# I2C_Shield.net
KiCad netlist of a schematic drawn in Altium Designer
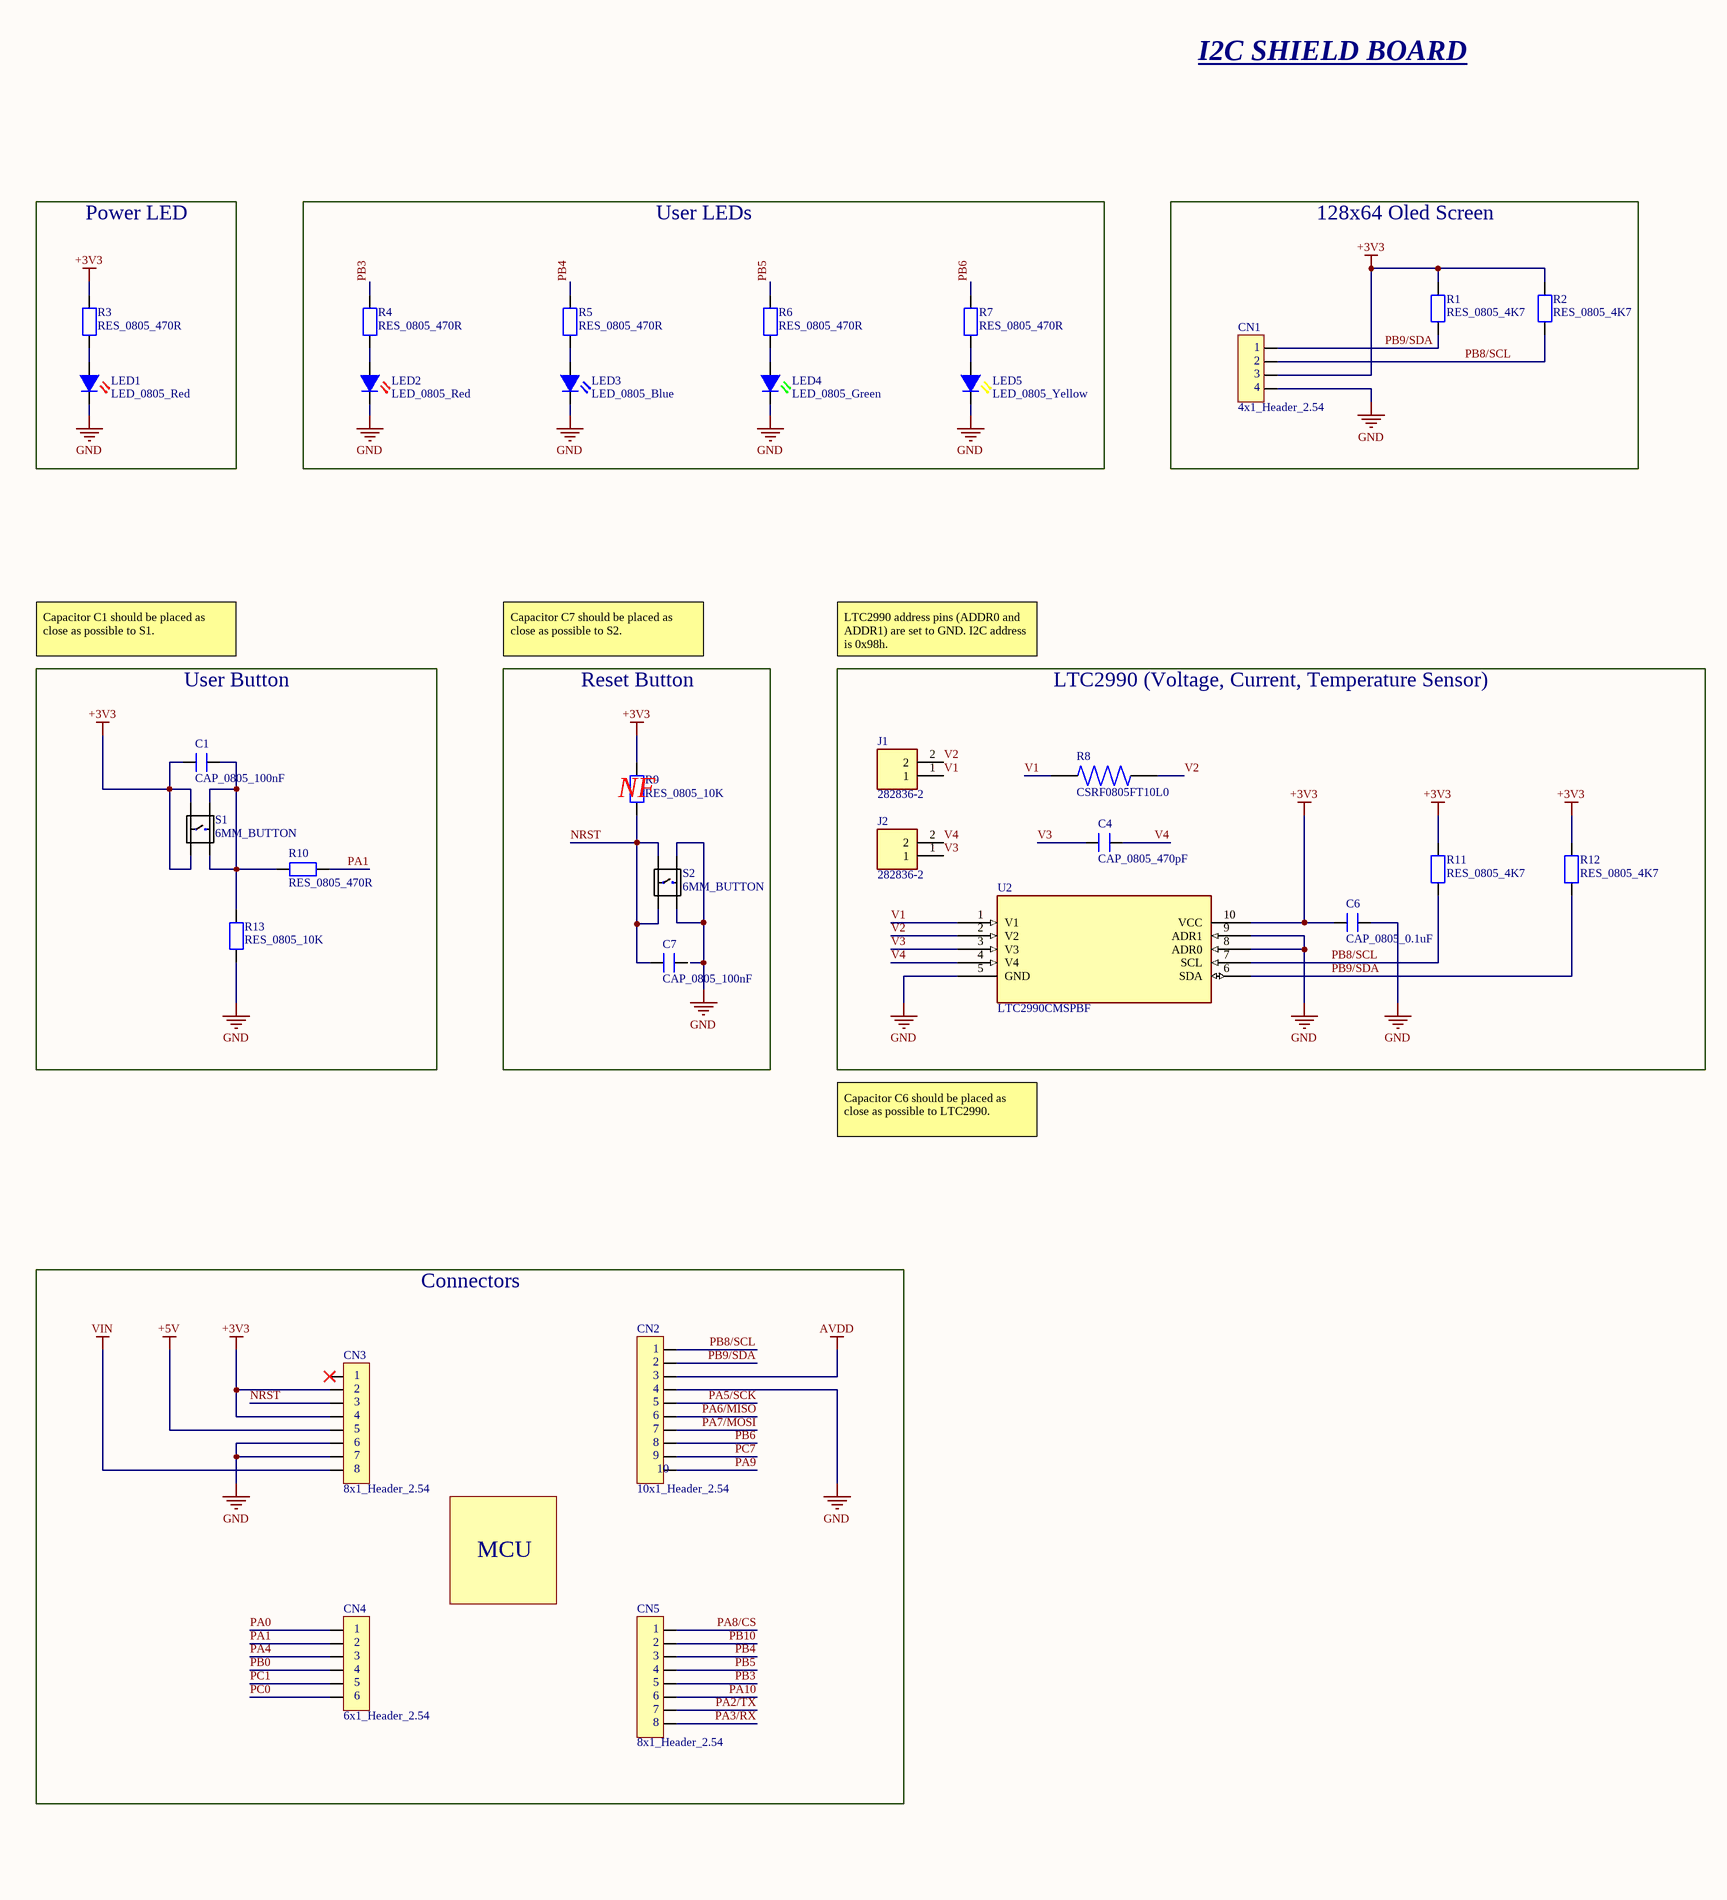
[diagram p0: I2C_Shield.SchDoc, left]
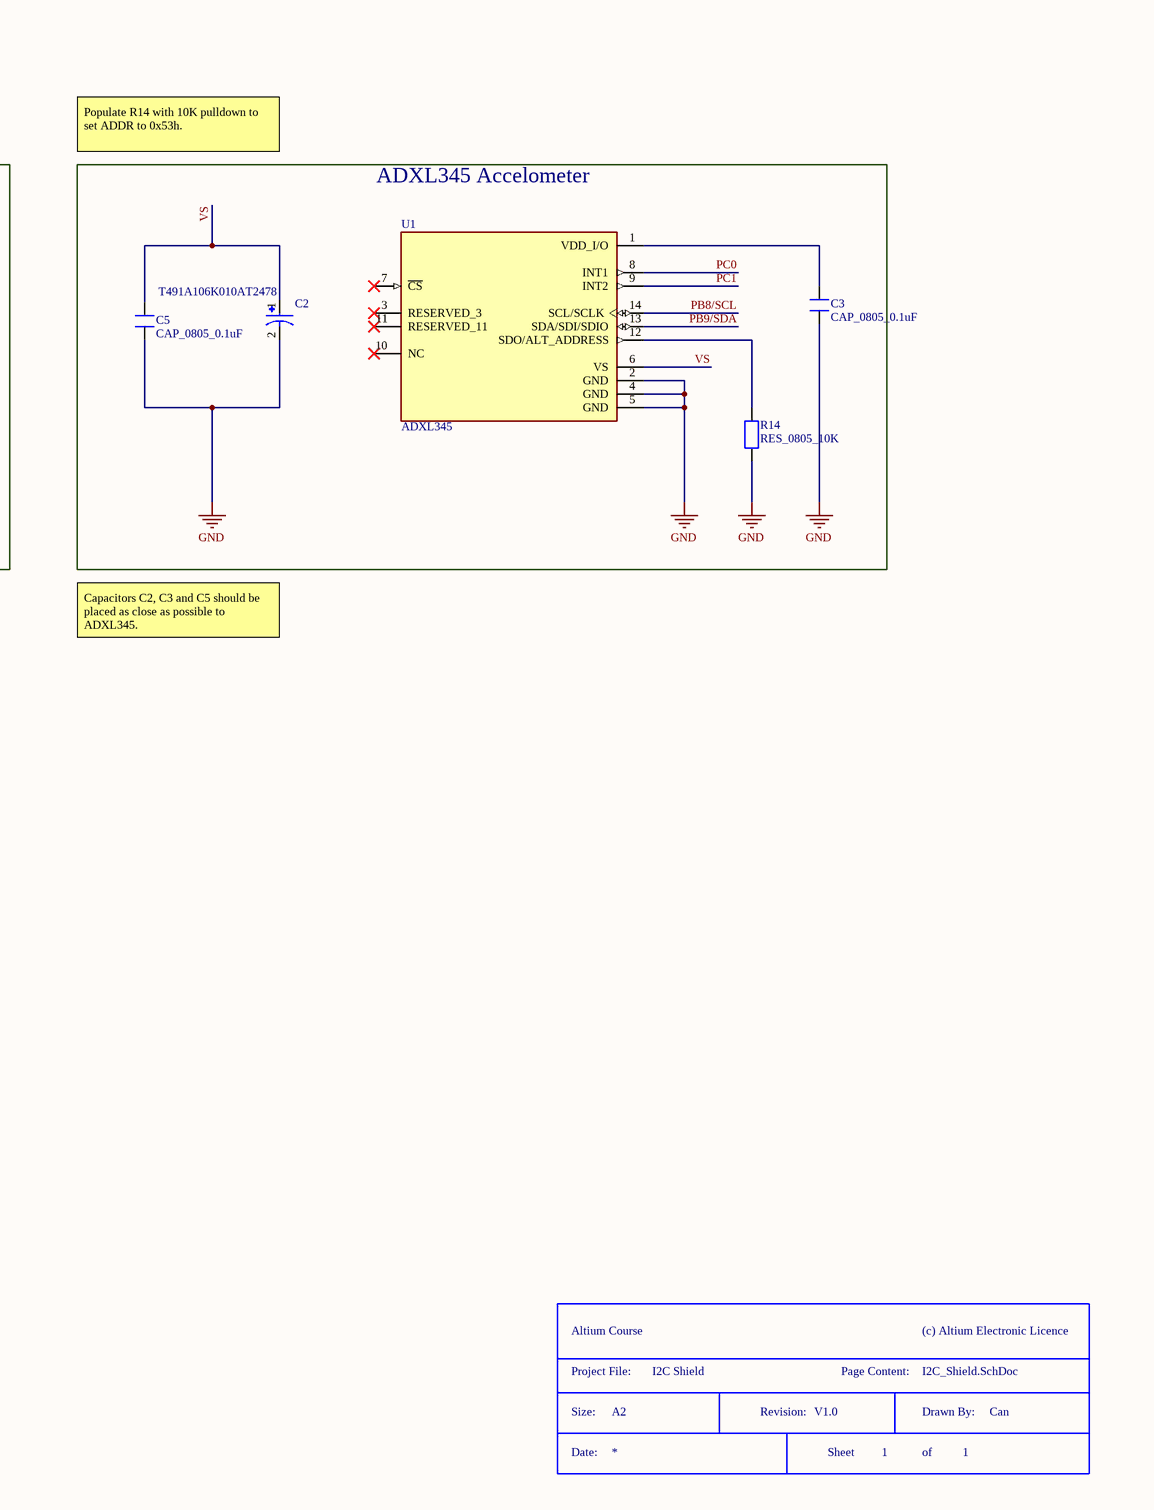
[diagram p1: I2C_Shield.SchDoc, right]

(export (version "E")
  (design (tool "Eeschema 10.0.6"))
  (components
    (comp (ref "*") (value "Title Block") (libsource (lib "I2C_Shield") (part "Title Block")))
    (comp (ref "C1")
      (value "CAP_0805_100nF")
      (footprint "CAP_0805")
      (description "0805 100nF 16VDC ±10% X7R")
      (fields (field (name "MANUFACTURER") "CC0805KRX7R7BB104") (field (name "TOLERANCE") "10%"))
      (libsource (lib "I2C_Shield") (part "CAP_0805_100nF"))
    )
    (comp (ref "C2")
      (value "T491A106K010AT2478")
      (footprint "CAPMP3216X180N")
      (description "10 ÂµF Molded Tantalum Capacitors 10 V 1206 (3216 Metric) 3.8Ohm")
      (fields (field (name "MF") "KEMET"))
      (libsource (lib "tantalum10uF") (part "T491A106K010AT2478"))
    )
    (comp (ref "C3")
      (value "CAP_0805_0.1uF")
      (footprint "CAP_0805")
      (description "0805 0.1uF 16VDC ±10% X7R")
      (fields (field (name "MANUFACTURER") "CC0805KRX7R7BB104") (field (name "TOLERANCE") "10%"))
      (libsource (lib "I2C_Shield") (part "CAP_0805_0.1uF"))
    )
    (comp (ref "C4")
      (value "CAP_0805_470pF")
      (footprint "CAP_0805")
      (description "0805 470pF 16VDC ±10% X7R")
      (fields (field (name "MANUFACTURER") "CC0805KRX7R7BB104") (field (name "TOLERANCE") "10%"))
      (libsource (lib "I2C_Shield") (part "CAP_0805_470pF"))
    )
    (comp (ref "C5")
      (value "CAP_0805_0.1uF")
      (footprint "CAP_0805")
      (description "0805 0.1uF 16VDC ±10% X7R")
      (fields (field (name "MANUFACTURER") "CC0805KRX7R7BB104") (field (name "TOLERANCE") "10%"))
      (libsource (lib "I2C_Shield") (part "CAP_0805_0.1uF"))
    )
    (comp (ref "C6")
      (value "CAP_0805_0.1uF")
      (footprint "CAP_0805")
      (description "0805 0.1uF 16VDC ±10% X7R")
      (fields (field (name "MANUFACTURER") "CC0805KRX7R7BB104") (field (name "TOLERANCE") "10%"))
      (libsource (lib "I2C_Shield") (part "CAP_0805_0.1uF"))
    )
    (comp (ref "C7")
      (value "CAP_0805_100nF")
      (footprint "CAP_0805")
      (description "0805 100nF 16VDC ±10% X7R")
      (fields (field (name "MANUFACTURER") "CC0805KRX7R7BB104") (field (name "TOLERANCE") "10%"))
      (libsource (lib "I2C_Shield") (part "CAP_0805_100nF"))
    )
    (comp (ref "CN1")
      (value "4x1_Header_2.54")
      (description "Oled Screen Header")
      (libsource (lib "I2C_Shield") (part "4x1_Header_2.54"))
    )
    (comp (ref "CN2")
      (value "10x1_Header_2.54")
      (footprint "10x1_2.54MM_HEADER")
      (libsource (lib "I2C_Shield") (part "10x1_Header_2.54"))
    )
    (comp (ref "CN3")
      (value "8x1_Header_2.54")
      (footprint "8x1_2.54MM_HEADER")
      (libsource (lib "I2C_Shield") (part "8x1_Header_2.54"))
    )
    (comp (ref "CN4")
      (value "6x1_Header_2.54")
      (footprint "6x1_2.54MM_HEADER")
      (libsource (lib "I2C_Shield") (part "6x1_Header_2.54"))
    )
    (comp (ref "CN5")
      (value "8x1_Header_2.54")
      (footprint "8x1_2.54MM_HEADER")
      (libsource (lib "") (part "8x1_Header_2.54_1"))
    )
    (comp (ref "J1")
      (value "282836-2")
      (footprint "TE_282836-2")
      (description "Connector, Terminal Block; Wire Receptacle; 2 Pos.; 16-30 AWG; 0.197 in. CL; Sid")
      (fields (field (name "MF") "TE Connectivity"))
      (libsource (lib "terminalblock-2") (part "282836-2"))
    )
    (comp (ref "J2")
      (value "282836-2")
      (footprint "TE_282836-2")
      (description "Connector, Terminal Block; Wire Receptacle; 2 Pos.; 16-30 AWG; 0.197 in. CL; Sid")
      (fields (field (name "MF") "TE Connectivity"))
      (libsource (lib "terminalblock-2") (part "282836-2"))
    )
    (comp (ref "LED1")
      (value "LED_0805_Red")
      (footprint "LED_0805")
      (description "LED SMD 0805 RED 550mcd")
      (fields (field (name "MANUFACTURER") "HL-PSC-2012S9AC"))
      (libsource (lib "I2C_Shield") (part "LED_0805_Red"))
    )
    (comp (ref "LED2")
      (value "LED_0805_Red")
      (footprint "LED_0805")
      (description "LED SMD 0805 RED 550mcd")
      (fields (field (name "MANUFACTURER") "HL-PSC-2012S9AC"))
      (libsource (lib "I2C_Shield") (part "LED_0805_Red"))
    )
    (comp (ref "LED3")
      (value "LED_0805_Blue")
      (footprint "LED_0805")
      (description "LED SMD 0805 BLUE 550mcd")
      (fields (field (name "MANUFACTURER") "HL-PSC-2012H203BC"))
      (libsource (lib "I2C_Shield") (part "LED_0805_Blue"))
    )
    (comp (ref "LED4")
      (value "LED_0805_Green")
      (footprint "LED_0805")
      (description "LED SMD 0805 GREEN 550mcd")
      (fields (field (name "MANUFACTURER") "HL-PSC-2012U51GC"))
      (libsource (lib "I2C_Shield") (part "LED_0805_Green"))
    )
    (comp (ref "LED5")
      (value "LED_0805_Yellow")
      (footprint "LED_0805")
      (description "LED SMD 0805 YELLOW 550mcd")
      (fields (field (name "MANUFACTURER") "HL-PSC-2012S29YC"))
      (libsource (lib "I2C_Shield") (part "LED_0805_Yellow"))
    )
    (comp (ref "R1")
      (value "RES_0805_4K7")
      (footprint "RES_0805")
      (description "0805 4K7 Ohms 5% 1/8W")
      (fields (field (name "TOLERANCE") "5%") (field (name "MANUFACTURER") "RC0805JR-0710KL"))
      (libsource (lib "I2C_Shield") (part "RES_0805_4K7"))
    )
    (comp (ref "R2")
      (value "RES_0805_4K7")
      (footprint "RES_0805")
      (description "0805 4K7 Ohms 5% 1/8W")
      (fields (field (name "TOLERANCE") "5%") (field (name "MANUFACTURER") "RC0805JR-0710KL"))
      (libsource (lib "I2C_Shield") (part "RES_0805_4K7"))
    )
    (comp (ref "R3")
      (value "RES_0805_470R")
      (footprint "RES_0805")
      (description "0805 470 Ohms 5% 1/8W")
      (fields (field (name "MANUFACTURER") "RC0805JR-07470RL") (field (name "TOLERANCE") "5%"))
      (libsource (lib "I2C_Shield") (part "RES_0805_470R"))
    )
    (comp (ref "R4")
      (value "RES_0805_470R")
      (footprint "RES_0805")
      (description "0805 470 Ohms 5% 1/8W")
      (fields (field (name "MANUFACTURER") "RC0805JR-07470RL") (field (name "TOLERANCE") "5%"))
      (libsource (lib "I2C_Shield") (part "RES_0805_470R"))
    )
    (comp (ref "R5")
      (value "RES_0805_470R")
      (footprint "RES_0805")
      (description "0805 470 Ohms 5% 1/8W")
      (fields (field (name "MANUFACTURER") "RC0805JR-07470RL") (field (name "TOLERANCE") "5%"))
      (libsource (lib "I2C_Shield") (part "RES_0805_470R"))
    )
    (comp (ref "R6")
      (value "RES_0805_470R")
      (footprint "RES_0805")
      (description "0805 470 Ohms 5% 1/8W")
      (fields (field (name "MANUFACTURER") "RC0805JR-07470RL") (field (name "TOLERANCE") "5%"))
      (libsource (lib "I2C_Shield") (part "RES_0805_470R"))
    )
    (comp (ref "R7")
      (value "RES_0805_470R")
      (footprint "RES_0805")
      (description "0805 470 Ohms 5% 1/8W")
      (fields (field (name "MANUFACTURER") "RC0805JR-07470RL") (field (name "TOLERANCE") "5%"))
      (libsource (lib "I2C_Shield") (part "RES_0805_470R"))
    )
    (comp (ref "R8")
      (value "CSRF0805FT10L0")
      (footprint "RESC2113X85N")
      (fields (field (name "MF") "Stackpole Electronics"))
      (libsource (lib "CSRF0805FT10L0") (part "CSRF0805FT10L0"))
    )
    (comp (ref "R9")
      (value "RES_0805_10K")
      (footprint "RES_0805")
      (description "0805 10K Ohms 5% 1/8W")
      (fields (field (name "TOLERANCE") "5%") (field (name "MANUFACTURER") "RC0805JR-0710KL"))
      (libsource (lib "I2C_Shield") (part "RES_0805_10K"))
    )
    (comp (ref "R10")
      (value "RES_0805_470R")
      (footprint "RES_0805")
      (description "0805 470 Ohms 5% 1/8W")
      (fields (field (name "MANUFACTURER") "RC0805JR-07470RL") (field (name "TOLERANCE") "5%"))
      (libsource (lib "I2C_Shield") (part "RES_0805_470R"))
    )
    (comp (ref "R11")
      (value "RES_0805_4K7")
      (footprint "RES_0805")
      (description "0805 4K7 Ohms 5% 1/8W")
      (fields (field (name "TOLERANCE") "5%") (field (name "MANUFACTURER") "RC0805JR-0710KL"))
      (libsource (lib "I2C_Shield") (part "RES_0805_4K7"))
    )
    (comp (ref "R12")
      (value "RES_0805_4K7")
      (footprint "RES_0805")
      (description "0805 4K7 Ohms 5% 1/8W")
      (fields (field (name "TOLERANCE") "5%") (field (name "MANUFACTURER") "RC0805JR-0710KL"))
      (libsource (lib "I2C_Shield") (part "RES_0805_4K7"))
    )
    (comp (ref "R13")
      (value "RES_0805_10K")
      (footprint "RES_0805")
      (description "0805 10K Ohms 5% 1/8W")
      (fields (field (name "TOLERANCE") "5%") (field (name "MANUFACTURER") "RC0805JR-0710KL"))
      (libsource (lib "I2C_Shield") (part "RES_0805_10K"))
    )
    (comp (ref "R14")
      (value "RES_0805_10K")
      (footprint "RES_0805")
      (description "0805 10K Ohms 5% 1/8W")
      (fields (field (name "TOLERANCE") "5%") (field (name "MANUFACTURER") "RC0805JR-0710KL"))
      (libsource (lib "I2C_Shield") (part "RES_0805_10K"))
    )
    (comp (ref "S1")
      (value "6MM_BUTTON")
      (footprint "6MM_TACTILE_SWITCH")
      (description "SWITCH TACT 6x6MM")
      (fields (field (name "MANUFACTURER") "DS1042-03-116-KKR-250-10"))
      (libsource (lib "I2C_Shield") (part "6MM_BUTTON"))
    )
    (comp (ref "S2")
      (value "6MM_BUTTON")
      (footprint "6MM_TACTILE_SWITCH")
      (description "SWITCH TACT 6x6MM")
      (fields (field (name "MANUFACTURER") "DS1042-03-116-KKR-250-10"))
      (libsource (lib "I2C_Shield") (part "6MM_BUTTON"))
    )
    (comp (ref "U1")
      (value "ADXL345")
      (footprint "PQFN80P500X300X100-14N")
      (description "Accelerometer X, Y, Z Axis ±2g, 4g, 8g, 16g 0.05Hz ~ 1.6kHz 14-LGA (3x5)")
      (fields (field (name "MF") "Analog Devices, Inc."))
      (libsource (lib "ADXL345") (part "ADXL345"))
    )
    (comp (ref "U2")
      (value "LTC2990CMSPBF")
      (footprint "MSOP-10_MS")
      (fields (field (name "MF") "Analog Devices") (field (name "MP") "LTC2990CMS#PBF"))
      (libsource (lib "LTC2990CMSPBF") (part "LTC2990CMSPBF"))
    )
  )
  (nets
    (net (code "1") (name "+3V3") (class "Default")
      (node (ref "C1") (pin "1") (pinfunction "1_1") (pintype "passive"))
      (node (ref "C6") (pin "1") (pinfunction "1_1") (pintype "passive"))
      (node (ref "CN1") (pin "2") (pinfunction "2_2") (pintype "passive"))
      (node (ref "CN3") (pin "2") (pinfunction "2_2") (pintype "passive"))
      (node (ref "CN3") (pin "4") (pinfunction "4_4") (pintype "passive"))
      (node (ref "R1") (pin "2") (pinfunction "2_2") (pintype "passive"))
      (node (ref "R11") (pin "1") (pinfunction "1_1") (pintype "passive"))
      (node (ref "R12") (pin "2") (pinfunction "2_2") (pintype "passive"))
      (node (ref "R2") (pin "2") (pinfunction "2_2") (pintype "passive"))
      (node (ref "R3") (pin "2") (pinfunction "2_2") (pintype "passive"))
      (node (ref "R9") (pin "2") (pinfunction "2_2") (pintype "passive"))
      (node (ref "S1") (pin "1") (pinfunction "1_1") (pintype "passive"))
      (node (ref "S1") (pin "3") (pinfunction "3_3") (pintype "passive"))
      (node (ref "U2") (pin "10") (pinfunction "VCC_10") (pintype "power_in"))
    )
    (net (code "2") (name "+5V") (class "Default")
      (node (ref "CN3") (pin "5") (pinfunction "5_5") (pintype "passive"))
    )
    (net (code "3") (name "/NRST") (class "Default")
      (node (ref "C7") (pin "1") (pinfunction "1_1") (pintype "passive"))
      (node (ref "CN3") (pin "3") (pinfunction "3_3") (pintype "passive"))
      (node (ref "R9") (pin "1") (pinfunction "1_1") (pintype "passive"))
      (node (ref "S2") (pin "1") (pinfunction "1_1") (pintype "passive"))
      (node (ref "S2") (pin "3") (pinfunction "3_3") (pintype "passive"))
    )
    (net (code "4") (name "/PA0") (class "Default")
      (node (ref "CN4") (pin "1") (pinfunction "1_1") (pintype "passive"))
    )
    (net (code "5") (name "/PA1") (class "Default")
      (node (ref "CN4") (pin "2") (pinfunction "2_2") (pintype "passive"))
      (node (ref "R10") (pin "2") (pinfunction "2_2") (pintype "passive"))
    )
    (net (code "6") (name "/PA2{slash}TX") (class "Default")
      (node (ref "CN5") (pin "7") (pinfunction "7_7") (pintype "passive"))
    )
    (net (code "7") (name "/PA3{slash}RX") (class "Default")
      (node (ref "CN5") (pin "8") (pinfunction "8_8") (pintype "passive"))
    )
    (net (code "8") (name "/PA4") (class "Default")
      (node (ref "CN4") (pin "3") (pinfunction "3_3") (pintype "passive"))
    )
    (net (code "9") (name "/PA5{slash}SCK") (class "Default")
      (node (ref "CN2") (pin "5") (pinfunction "5_5") (pintype "passive"))
    )
    (net (code "10") (name "/PA6{slash}MISO") (class "Default")
      (node (ref "CN2") (pin "6") (pinfunction "6_6") (pintype "passive"))
    )
    (net (code "11") (name "/PA7{slash}MOSI") (class "Default")
      (node (ref "CN2") (pin "7") (pinfunction "7_7") (pintype "passive"))
    )
    (net (code "12") (name "/PA8{slash}CS") (class "Default")
      (node (ref "CN5") (pin "1") (pinfunction "1_1") (pintype "passive"))
    )
    (net (code "13") (name "/PA9") (class "Default")
      (node (ref "CN2") (pin "10") (pinfunction "10_10") (pintype "passive"))
    )
    (net (code "14") (name "/PA10") (class "Default")
      (node (ref "CN5") (pin "6") (pinfunction "6_6") (pintype "passive"))
    )
    (net (code "15") (name "/PB0") (class "Default")
      (node (ref "CN4") (pin "4") (pinfunction "4_4") (pintype "passive"))
    )
    (net (code "16") (name "/PB3") (class "Default")
      (node (ref "CN5") (pin "5") (pinfunction "5_5") (pintype "passive"))
      (node (ref "R4") (pin "2") (pinfunction "2_2") (pintype "passive"))
    )
    (net (code "17") (name "/PB4") (class "Default")
      (node (ref "CN5") (pin "3") (pinfunction "3_3") (pintype "passive"))
      (node (ref "R5") (pin "2") (pinfunction "2_2") (pintype "passive"))
    )
    (net (code "18") (name "/PB5") (class "Default")
      (node (ref "CN5") (pin "4") (pinfunction "4_4") (pintype "passive"))
      (node (ref "R6") (pin "1") (pinfunction "1_1") (pintype "passive"))
    )
    (net (code "19") (name "/PB6") (class "Default")
      (node (ref "CN2") (pin "8") (pinfunction "8_8") (pintype "passive"))
      (node (ref "R7") (pin "2") (pinfunction "2_2") (pintype "passive"))
    )
    (net (code "20") (name "/PB8{slash}SCL") (class "Default")
      (node (ref "CN1") (pin "1") (pinfunction "1_1") (pintype "passive"))
      (node (ref "CN2") (pin "1") (pinfunction "1_1") (pintype "passive"))
      (node (ref "R11") (pin "2") (pinfunction "2_2") (pintype "passive"))
      (node (ref "R2") (pin "1") (pinfunction "1_1") (pintype "passive"))
      (node (ref "U1") (pin "14") (pinfunction "SCL/SCLK_14") (pintype "bidirectional"))
      (node (ref "U2") (pin "7") (pinfunction "SCL_7") (pintype "input"))
    )
    (net (code "21") (name "/PB9{slash}SDA") (class "Default")
      (node (ref "CN1") (pin "0") (pinfunction "0_0") (pintype "passive"))
      (node (ref "CN2") (pin "2") (pinfunction "2_2") (pintype "passive"))
      (node (ref "R1") (pin "1") (pinfunction "1_1") (pintype "passive"))
      (node (ref "R12") (pin "1") (pinfunction "1_1") (pintype "passive"))
      (node (ref "U1") (pin "13") (pinfunction "SDA/SDI/SDIO_13") (pintype "bidirectional"))
      (node (ref "U2") (pin "6") (pinfunction "SDA_6") (pintype "bidirectional"))
    )
    (net (code "22") (name "/PB10") (class "Default")
      (node (ref "CN5") (pin "2") (pinfunction "2_2") (pintype "passive"))
    )
    (net (code "23") (name "/PC0") (class "Default")
      (node (ref "CN4") (pin "6") (pinfunction "6_6") (pintype "passive"))
      (node (ref "U1") (pin "8") (pinfunction "INT1_8") (pintype "output"))
    )
    (net (code "24") (name "/PC1") (class "Default")
      (node (ref "CN4") (pin "5") (pinfunction "5_5") (pintype "passive"))
      (node (ref "U1") (pin "9") (pinfunction "INT2_9") (pintype "output"))
    )
    (net (code "25") (name "/PC7") (class "Default")
      (node (ref "CN2") (pin "9") (pinfunction "9_9") (pintype "passive"))
    )
    (net (code "26") (name "/V1") (class "Default")
      (node (ref "J1") (pin "1") (pinfunction "1_1") (pintype "passive"))
      (node (ref "R8") (pin "1") (pinfunction "1_1") (pintype "passive"))
      (node (ref "U2") (pin "1") (pinfunction "V1_1") (pintype "input"))
    )
    (net (code "27") (name "/V2") (class "Default")
      (node (ref "J1") (pin "2") (pinfunction "2_2") (pintype "passive"))
      (node (ref "R8") (pin "2") (pinfunction "2_2") (pintype "passive"))
      (node (ref "U2") (pin "2") (pinfunction "V2_2") (pintype "input"))
    )
    (net (code "28") (name "/V3") (class "Default")
      (node (ref "C4") (pin "1") (pinfunction "1_1") (pintype "passive"))
      (node (ref "J2") (pin "1") (pinfunction "1_1") (pintype "passive"))
      (node (ref "U2") (pin "3") (pinfunction "V3_3") (pintype "input"))
    )
    (net (code "29") (name "/V4") (class "Default")
      (node (ref "C4") (pin "2") (pinfunction "2_2") (pintype "passive"))
      (node (ref "J2") (pin "2") (pinfunction "2_2") (pintype "passive"))
      (node (ref "U2") (pin "4") (pinfunction "V4_4") (pintype "input"))
    )
    (net (code "30") (name "/VS") (class "Default")
      (node (ref "C2") (pin "1") (pinfunction "1_1") (pintype "passive"))
      (node (ref "C5") (pin "2") (pinfunction "2_2") (pintype "passive"))
      (node (ref "U1") (pin "6") (pinfunction "VS_6") (pintype "power_in"))
    )
    (net (code "31") (name "AVDD") (class "Default")
      (node (ref "CN2") (pin "3") (pinfunction "3_3") (pintype "passive"))
    )
    (net (code "32") (name "GND") (class "Default")
      (node (ref "C2") (pin "2") (pinfunction "2_2") (pintype "passive"))
      (node (ref "C3") (pin "2") (pinfunction "2_2") (pintype "passive"))
      (node (ref "C5") (pin "1") (pinfunction "1_1") (pintype "passive"))
      (node (ref "C6") (pin "2") (pinfunction "2_2") (pintype "passive"))
      (node (ref "CN1") (pin "3") (pinfunction "3_3") (pintype "passive"))
      (node (ref "CN2") (pin "4") (pinfunction "4_4") (pintype "passive"))
      (node (ref "CN3") (pin "6") (pinfunction "6_6") (pintype "passive"))
      (node (ref "CN3") (pin "7") (pinfunction "7_7") (pintype "passive"))
      (node (ref "LED1") (pin "C") (pinfunction "C_C") (pintype "passive"))
      (node (ref "LED2") (pin "C") (pinfunction "C_C") (pintype "passive"))
      (node (ref "LED3") (pin "C") (pinfunction "C_C") (pintype "passive"))
      (node (ref "LED4") (pin "C") (pinfunction "C_C") (pintype "passive"))
      (node (ref "LED5") (pin "C") (pinfunction "C_C") (pintype "passive"))
      (node (ref "R13") (pin "1") (pinfunction "1_1") (pintype "passive"))
      (node (ref "R14") (pin "1") (pinfunction "1_1") (pintype "passive"))
      (node (ref "S2") (pin "2") (pinfunction "2_2") (pintype "passive"))
      (node (ref "S2") (pin "4") (pinfunction "4_4") (pintype "passive"))
      (node (ref "U1") (pin "2") (pinfunction "GND_2") (pintype "power_in"))
      (node (ref "U1") (pin "4") (pinfunction "GND_4") (pintype "power_in"))
      (node (ref "U1") (pin "5") (pinfunction "GND_5") (pintype "power_in"))
      (node (ref "U2") (pin "5") (pinfunction "GND_5") (pintype "power_in"))
      (node (ref "U2") (pin "8") (pinfunction "ADR0_8") (pintype "input"))
      (node (ref "U2") (pin "9") (pinfunction "ADR1_9") (pintype "input"))
    )
    (net (code "33") (name "Net-(C1-Pad2)") (class "Default")
      (node (ref "C1") (pin "2") (pinfunction "2_2") (pintype "passive"))
      (node (ref "R10") (pin "1") (pinfunction "1_1") (pintype "passive"))
      (node (ref "R13") (pin "2") (pinfunction "2_2") (pintype "passive"))
      (node (ref "S1") (pin "2") (pinfunction "2_2") (pintype "passive"))
      (node (ref "S1") (pin "4") (pinfunction "4_4") (pintype "passive"))
    )
    (net (code "34") (name "Net-(LED1-PadA)") (class "Default")
      (node (ref "LED1") (pin "A") (pinfunction "A_A") (pintype "passive"))
      (node (ref "R3") (pin "1") (pinfunction "1_1") (pintype "passive"))
    )
    (net (code "35") (name "Net-(LED2-PadA)") (class "Default")
      (node (ref "LED2") (pin "A") (pinfunction "A_A") (pintype "passive"))
      (node (ref "R4") (pin "1") (pinfunction "1_1") (pintype "passive"))
    )
    (net (code "36") (name "Net-(LED3-PadA)") (class "Default")
      (node (ref "LED3") (pin "A") (pinfunction "A_A") (pintype "passive"))
      (node (ref "R5") (pin "1") (pinfunction "1_1") (pintype "passive"))
    )
    (net (code "37") (name "Net-(LED4-PadA)") (class "Default")
      (node (ref "LED4") (pin "A") (pinfunction "A_A") (pintype "passive"))
      (node (ref "R6") (pin "2") (pinfunction "2_2") (pintype "passive"))
    )
    (net (code "38") (name "Net-(LED5-PadA)") (class "Default")
      (node (ref "LED5") (pin "A") (pinfunction "A_A") (pintype "passive"))
      (node (ref "R7") (pin "1") (pinfunction "1_1") (pintype "passive"))
    )
    (net (code "39") (name "Net-(U1-SDO{slash}ALT_ADDRESS)") (class "Default")
      (node (ref "R14") (pin "2") (pinfunction "2_2") (pintype "passive"))
      (node (ref "U1") (pin "12") (pinfunction "SDO/ALT_ADDRESS_12") (pintype "output"))
    )
    (net (code "40") (name "Net-(U1-VDD_I{slash}O)") (class "Default")
      (node (ref "C3") (pin "1") (pinfunction "1_1") (pintype "passive"))
      (node (ref "U1") (pin "1") (pinfunction "VDD_I/O_1") (pintype "power_in"))
    )
    (net (code "41") (name "VIN") (class "Default")
      (node (ref "CN3") (pin "8") (pinfunction "8_8") (pintype "passive"))
    )
    (net (code "42") (name "unconnected-(C7-Pad2)") (class "Default")
      (node (ref "C7") (pin "2") (pinfunction "2_2") (pintype "passive"))
    )
    (net (code "43") (name "unconnected-(CN3-Pad1)") (class "Default")
      (node (ref "CN3") (pin "1") (pinfunction "1_1") (pintype "passive+no_connect"))
    )
    (net (code "44") (name "unconnected-(U1-NC-Pad10)") (class "Default")
      (node (ref "U1") (pin "10") (pinfunction "NC_10") (pintype "passive+no_connect"))
    )
    (net (code "45") (name "unconnected-(U1-RESERVED_3-Pad3)") (class "Default")
      (node (ref "U1") (pin "3") (pinfunction "RESERVED_3_3") (pintype "passive+no_connect"))
    )
    (net (code "46") (name "unconnected-(U1-RESERVED_11-Pad11)") (class "Default")
      (node (ref "U1") (pin "11") (pinfunction "RESERVED_11_11") (pintype "passive+no_connect"))
    )
    (net (code "47") (name "unconnected-(U1-~{CS}-Pad7)") (class "Default")
      (node (ref "U1") (pin "7") (pinfunction "~{CS}_7") (pintype "input+no_connect"))
    )
  )
)
